# isg-pico-filter-breakout-rev1.net
KiCad netlist of a schematic drawn in EAGLE
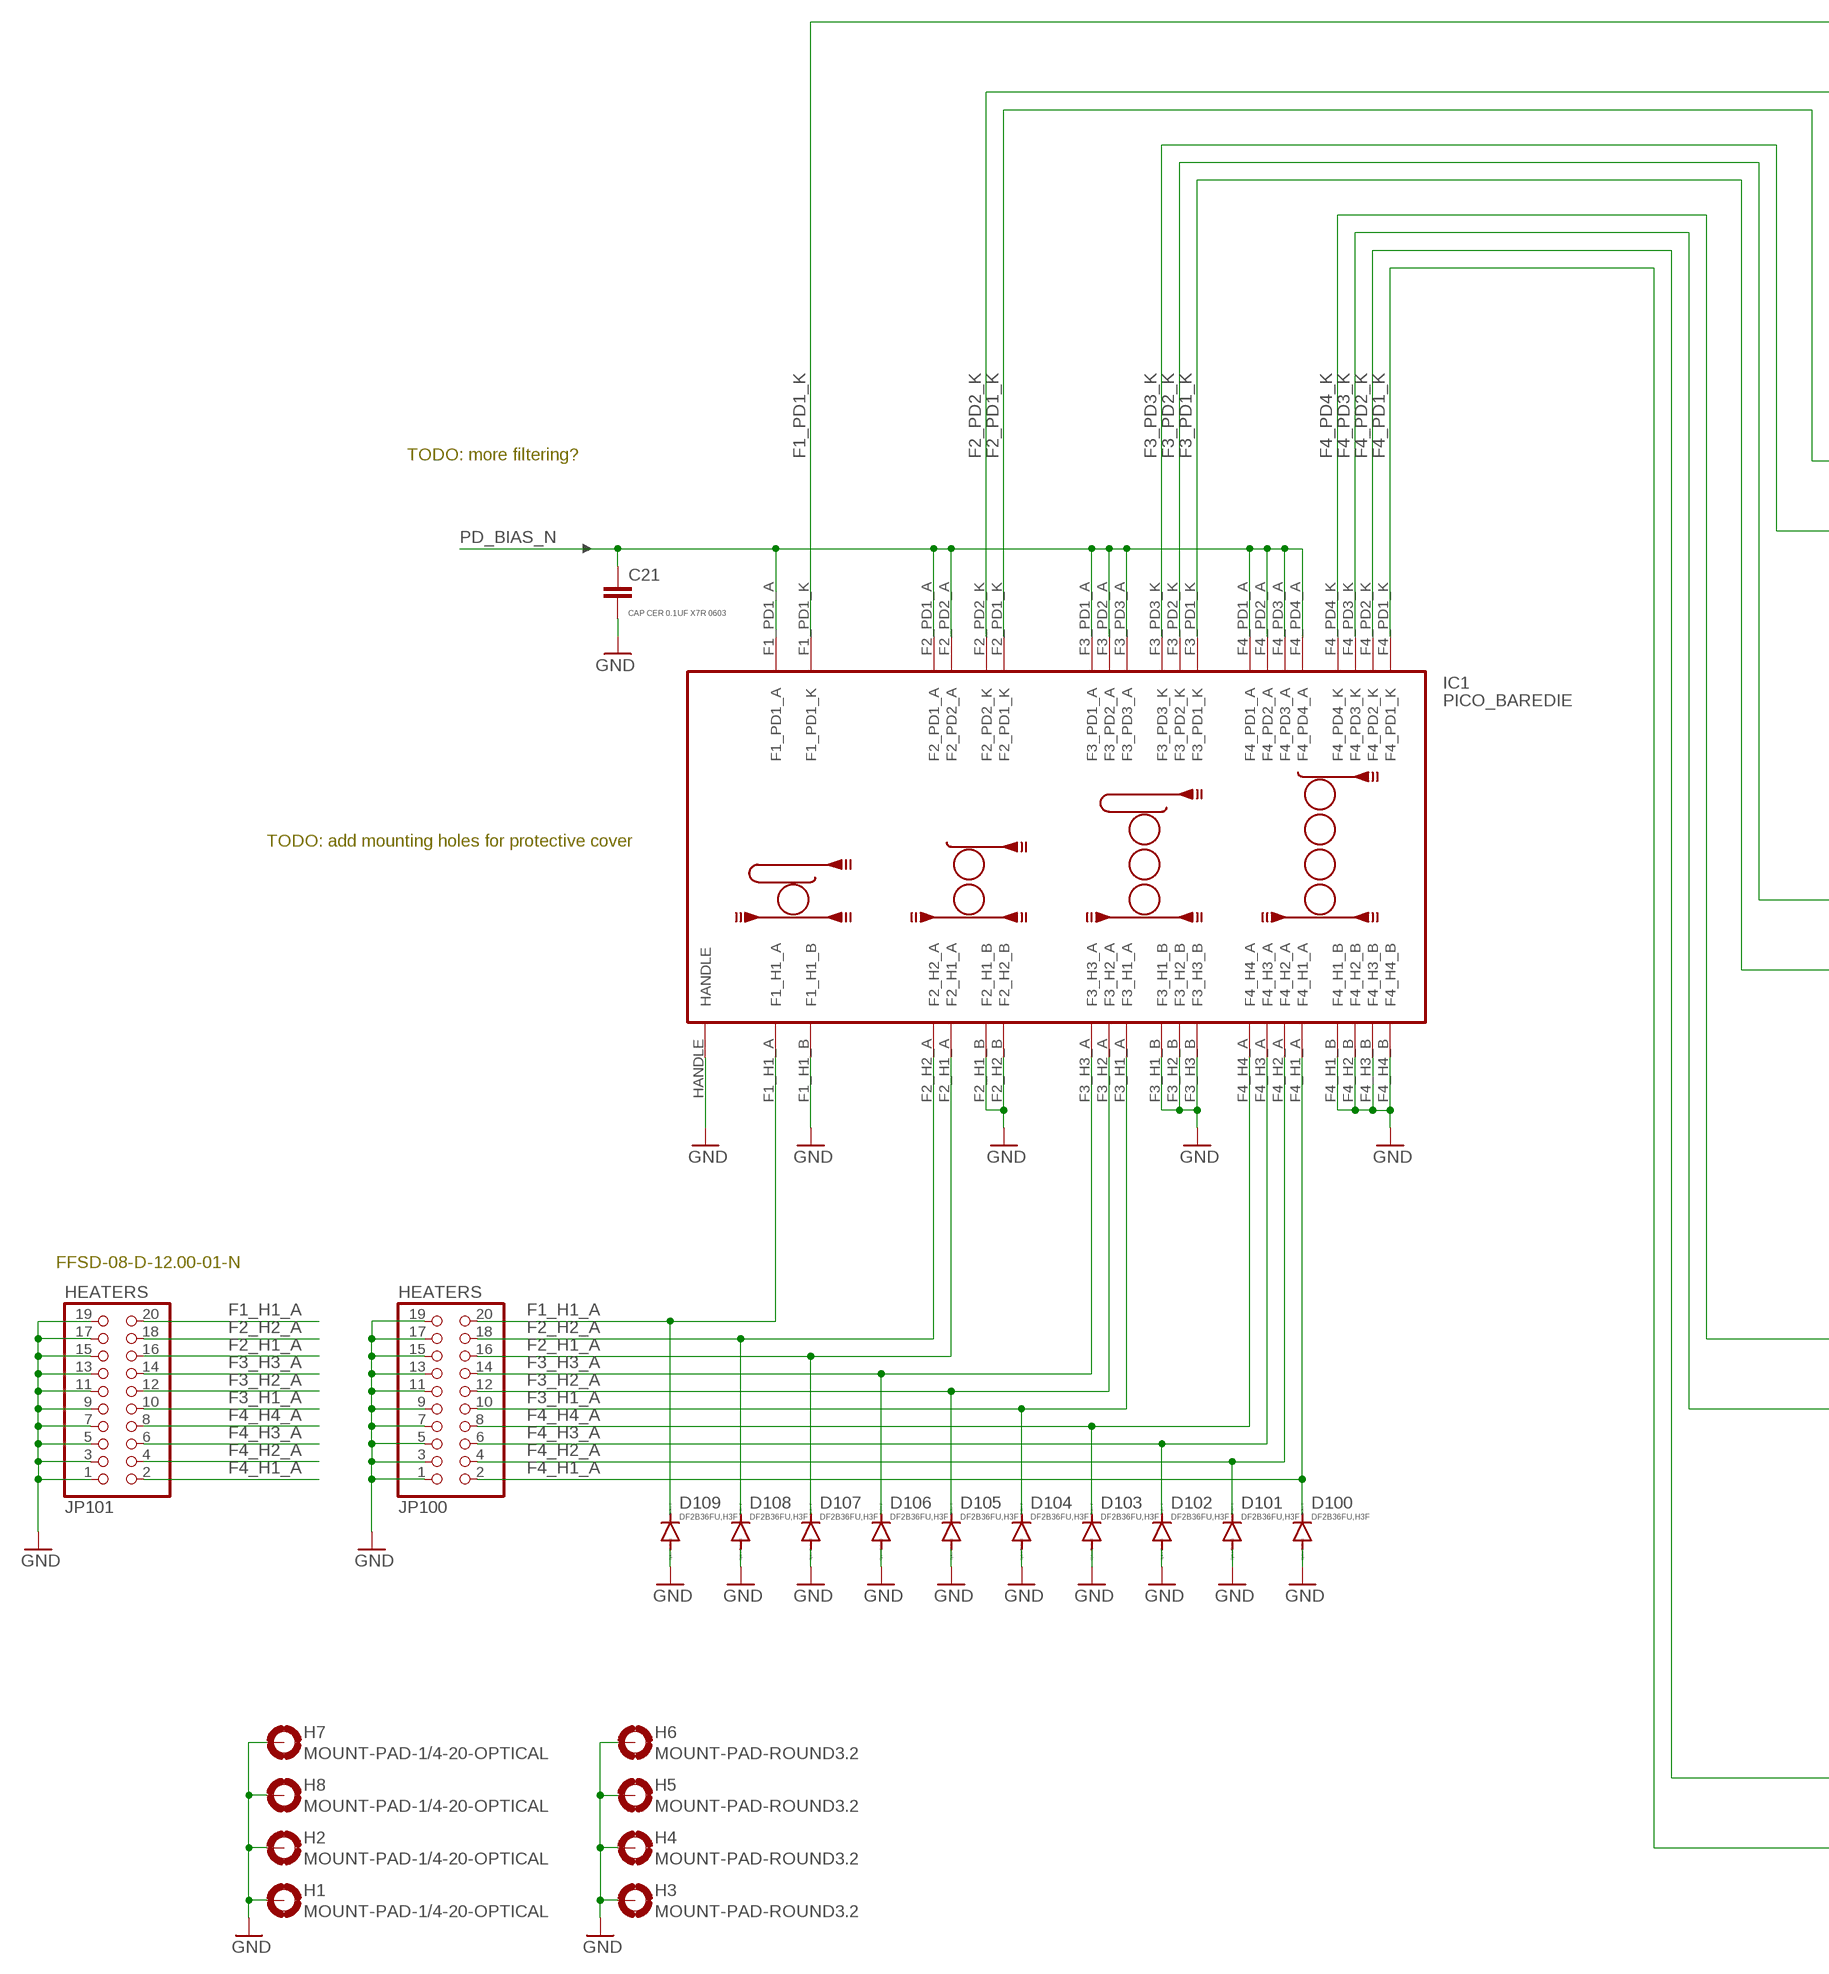
[diagram p0: schematic, sheet 1, part 1 of 2]
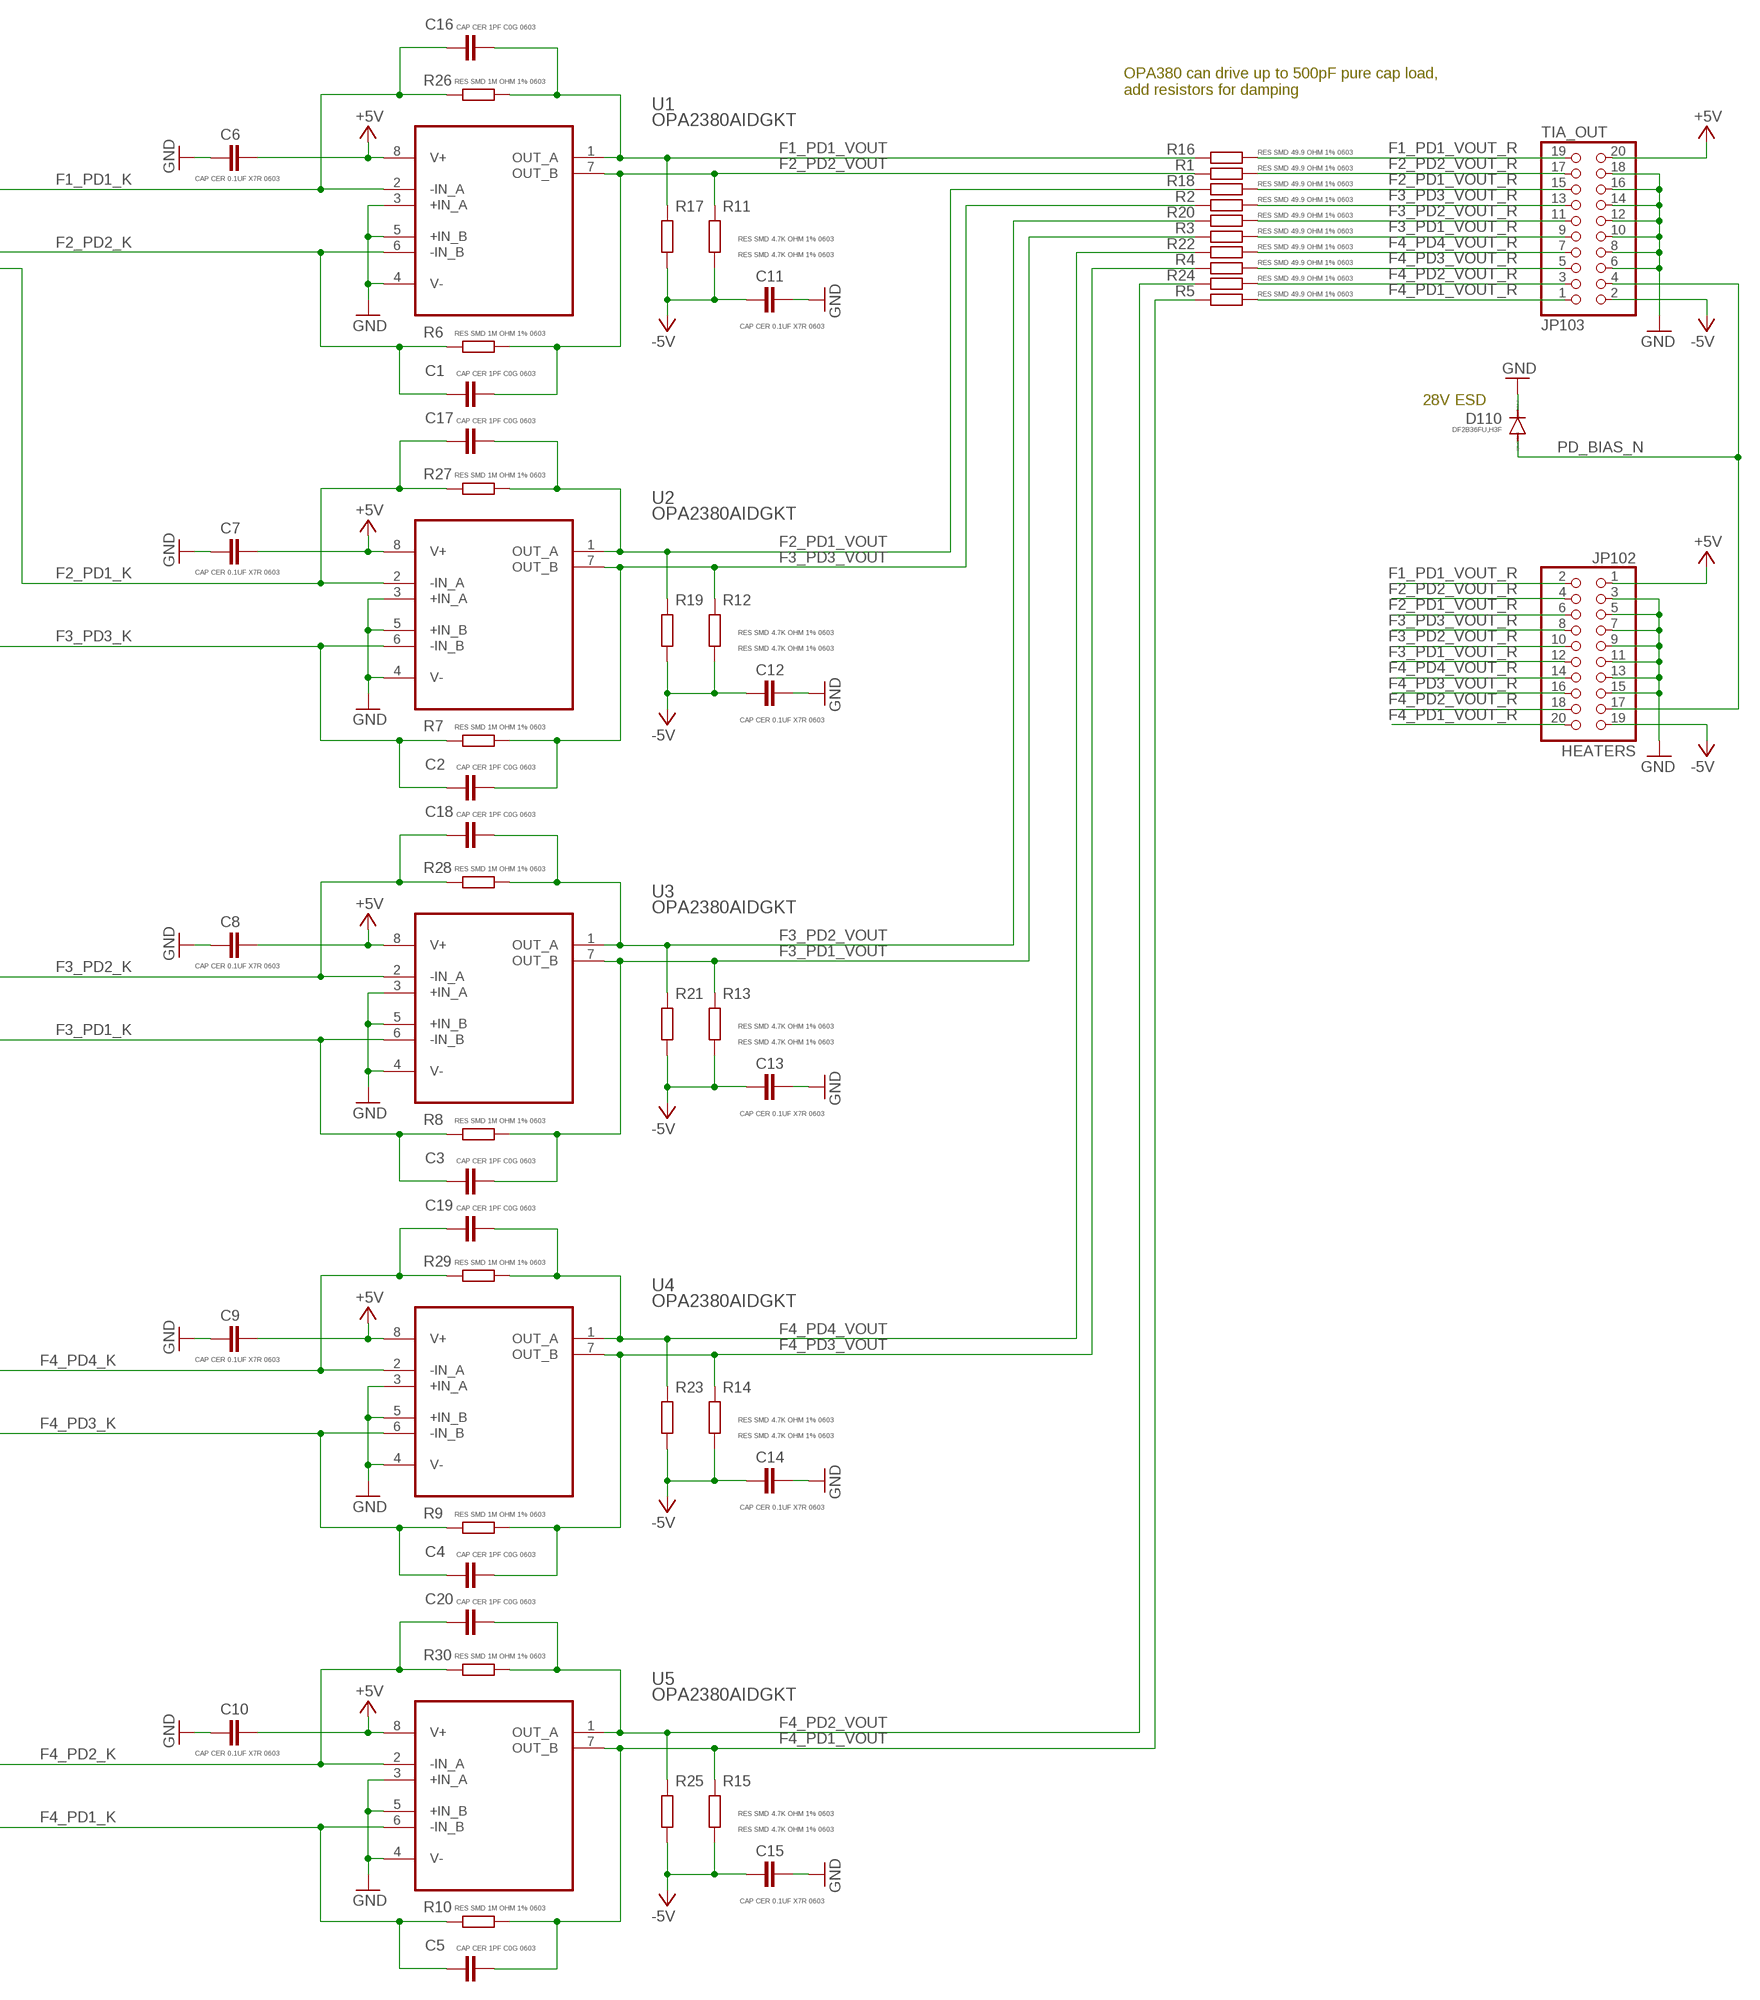
[diagram p1: schematic, sheet 1, part 2 of 2]

(export (version "E")
  (design (tool "Eeschema 10.0.6"))
  (components
    (comp (ref "C1")
      (value "CAP CER 1PF C0G 0603")
      (footprint "eagle-import:C0603")
      (libsource (lib "eagle-import") (part "C-EUC0603"))
    )
    (comp (ref "C2")
      (value "CAP CER 1PF C0G 0603")
      (footprint "eagle-import:C0603")
      (libsource (lib "eagle-import") (part "C-EUC0603"))
    )
    (comp (ref "C3")
      (value "CAP CER 1PF C0G 0603")
      (footprint "eagle-import:C0603")
      (libsource (lib "eagle-import") (part "C-EUC0603"))
    )
    (comp (ref "C4")
      (value "CAP CER 1PF C0G 0603")
      (footprint "eagle-import:C0603")
      (libsource (lib "eagle-import") (part "C-EUC0603"))
    )
    (comp (ref "C5")
      (value "CAP CER 1PF C0G 0603")
      (footprint "eagle-import:C0603")
      (libsource (lib "eagle-import") (part "C-EUC0603"))
    )
    (comp (ref "C6")
      (value "CAP CER 0.1UF X7R 0603")
      (footprint "eagle-import:C0603")
      (libsource (lib "eagle-import") (part "C-EUC0603"))
    )
    (comp (ref "C7")
      (value "CAP CER 0.1UF X7R 0603")
      (footprint "eagle-import:C0603")
      (libsource (lib "eagle-import") (part "C-EUC0603"))
    )
    (comp (ref "C8")
      (value "CAP CER 0.1UF X7R 0603")
      (footprint "eagle-import:C0603")
      (libsource (lib "eagle-import") (part "C-EUC0603"))
    )
    (comp (ref "C9")
      (value "CAP CER 0.1UF X7R 0603")
      (footprint "eagle-import:C0603")
      (libsource (lib "eagle-import") (part "C-EUC0603"))
    )
    (comp (ref "C10")
      (value "CAP CER 0.1UF X7R 0603")
      (footprint "eagle-import:C0603")
      (libsource (lib "eagle-import") (part "C-EUC0603"))
    )
    (comp (ref "C11")
      (value "CAP CER 0.1UF X7R 0603")
      (footprint "eagle-import:C0603")
      (libsource (lib "eagle-import") (part "C-EUC0603"))
    )
    (comp (ref "C12")
      (value "CAP CER 0.1UF X7R 0603")
      (footprint "eagle-import:C0603")
      (libsource (lib "eagle-import") (part "C-EUC0603"))
    )
    (comp (ref "C13")
      (value "CAP CER 0.1UF X7R 0603")
      (footprint "eagle-import:C0603")
      (libsource (lib "eagle-import") (part "C-EUC0603"))
    )
    (comp (ref "C14")
      (value "CAP CER 0.1UF X7R 0603")
      (footprint "eagle-import:C0603")
      (libsource (lib "eagle-import") (part "C-EUC0603"))
    )
    (comp (ref "C15")
      (value "CAP CER 0.1UF X7R 0603")
      (footprint "eagle-import:C0603")
      (libsource (lib "eagle-import") (part "C-EUC0603"))
    )
    (comp (ref "C16")
      (value "CAP CER 1PF C0G 0603")
      (footprint "eagle-import:C0603")
      (libsource (lib "eagle-import") (part "C-EUC0603"))
    )
    (comp (ref "C17")
      (value "CAP CER 1PF C0G 0603")
      (footprint "eagle-import:C0603")
      (libsource (lib "eagle-import") (part "C-EUC0603"))
    )
    (comp (ref "C18")
      (value "CAP CER 1PF C0G 0603")
      (footprint "eagle-import:C0603")
      (libsource (lib "eagle-import") (part "C-EUC0603"))
    )
    (comp (ref "C19")
      (value "CAP CER 1PF C0G 0603")
      (footprint "eagle-import:C0603")
      (libsource (lib "eagle-import") (part "C-EUC0603"))
    )
    (comp (ref "C20")
      (value "CAP CER 1PF C0G 0603")
      (footprint "eagle-import:C0603")
      (libsource (lib "eagle-import") (part "C-EUC0603"))
    )
    (comp (ref "C21")
      (value "CAP CER 0.1UF X7R 0603")
      (footprint "eagle-import:C0603")
      (libsource (lib "eagle-import") (part "C-EUC0603"))
    )
    (comp (ref "D100")
      (value "DF2B36FU,H3F")
      (footprint "eagle-import:SOD323-W")
      (libsource (lib "eagle-import") (part "DIODE-SOD323-W"))
    )
    (comp (ref "D101")
      (value "DF2B36FU,H3F")
      (footprint "eagle-import:SOD323-W")
      (libsource (lib "eagle-import") (part "DIODE-SOD323-W"))
    )
    (comp (ref "D102")
      (value "DF2B36FU,H3F")
      (footprint "eagle-import:SOD323-W")
      (libsource (lib "eagle-import") (part "DIODE-SOD323-W"))
    )
    (comp (ref "D103")
      (value "DF2B36FU,H3F")
      (footprint "eagle-import:SOD323-W")
      (libsource (lib "eagle-import") (part "DIODE-SOD323-W"))
    )
    (comp (ref "D104")
      (value "DF2B36FU,H3F")
      (footprint "eagle-import:SOD323-W")
      (libsource (lib "eagle-import") (part "DIODE-SOD323-W"))
    )
    (comp (ref "D105")
      (value "DF2B36FU,H3F")
      (footprint "eagle-import:SOD323-W")
      (libsource (lib "eagle-import") (part "DIODE-SOD323-W"))
    )
    (comp (ref "D106")
      (value "DF2B36FU,H3F")
      (footprint "eagle-import:SOD323-W")
      (libsource (lib "eagle-import") (part "DIODE-SOD323-W"))
    )
    (comp (ref "D107")
      (value "DF2B36FU,H3F")
      (footprint "eagle-import:SOD323-W")
      (libsource (lib "eagle-import") (part "DIODE-SOD323-W"))
    )
    (comp (ref "D108")
      (value "DF2B36FU,H3F")
      (footprint "eagle-import:SOD323-W")
      (libsource (lib "eagle-import") (part "DIODE-SOD323-W"))
    )
    (comp (ref "D109")
      (value "DF2B36FU,H3F")
      (footprint "eagle-import:SOD323-W")
      (libsource (lib "eagle-import") (part "DIODE-SOD323-W"))
    )
    (comp (ref "D110")
      (value "DF2B36FU,H3F")
      (footprint "eagle-import:SOD323-W")
      (libsource (lib "eagle-import") (part "DIODE-SOD323-W"))
    )
    (comp (ref "H1")
      (value "MOUNT-PAD-1/4-20-OPTICAL")
      (footprint "eagle-import:MOUNT-PAD-1_4-20")
      (libsource (lib "eagle-import") (part "MOUNT-PAD-1/4-20-OPTICAL"))
    )
    (comp (ref "H2")
      (value "MOUNT-PAD-1/4-20-OPTICAL")
      (footprint "eagle-import:MOUNT-PAD-1_4-20")
      (libsource (lib "eagle-import") (part "MOUNT-PAD-1/4-20-OPTICAL"))
    )
    (comp (ref "H3")
      (value "MOUNT-PAD-ROUND3.2")
      (footprint "eagle-import:3,2-PAD")
      (libsource (lib "eagle-import") (part "MOUNT-PAD-ROUND3.2"))
    )
    (comp (ref "H4")
      (value "MOUNT-PAD-ROUND3.2")
      (footprint "eagle-import:3,2-PAD")
      (libsource (lib "eagle-import") (part "MOUNT-PAD-ROUND3.2"))
    )
    (comp (ref "H5")
      (value "MOUNT-PAD-ROUND3.2")
      (footprint "eagle-import:3,2-PAD")
      (libsource (lib "eagle-import") (part "MOUNT-PAD-ROUND3.2"))
    )
    (comp (ref "H6")
      (value "MOUNT-PAD-ROUND3.2")
      (footprint "eagle-import:3,2-PAD")
      (libsource (lib "eagle-import") (part "MOUNT-PAD-ROUND3.2"))
    )
    (comp (ref "H7")
      (value "MOUNT-PAD-1/4-20-OPTICAL")
      (footprint "eagle-import:MOUNT-PAD-1_4-20")
      (libsource (lib "eagle-import") (part "MOUNT-PAD-1/4-20-OPTICAL"))
    )
    (comp (ref "H8")
      (value "MOUNT-PAD-1/4-20-OPTICAL")
      (footprint "eagle-import:MOUNT-PAD-1_4-20")
      (libsource (lib "eagle-import") (part "MOUNT-PAD-1/4-20-OPTICAL"))
    )
    (comp (ref "IC1")
      (value "PICO_BAREDIE")
      (footprint "eagle-import:DIE-PICO-MULTI-RING-FILTERS")
      (libsource (lib "eagle-import") (part "DIE-PICO-MULTI-RING-FILTERS"))
    )
    (comp (ref "JP100")
      (value "HEATERS")
      (footprint "eagle-import:2X10")
      (libsource (lib "eagle-import") (part "PINHD-2X10"))
    )
    (comp (ref "JP101")
      (value "HEATERS")
      (footprint "eagle-import:FTSH-110-01-L-DV-K-TR")
      (libsource (lib "eagle-import") (part "FFSD-08-D-12.00-01-N"))
    )
    (comp (ref "JP102")
      (value "HEATERS")
      (footprint "eagle-import:FTSH-110-01-L-DV-K-TR")
      (libsource (lib "eagle-import") (part "FFSD-08-D-12.00-01-N"))
    )
    (comp (ref "JP103")
      (value "TIA_OUT")
      (footprint "eagle-import:2X10")
      (libsource (lib "eagle-import") (part "PINHD-2X10"))
    )
    (comp (ref "R1")
      (value "RES SMD 49.9 OHM 1% 0603")
      (footprint "eagle-import:R0603")
      (libsource (lib "eagle-import") (part "R-EU_R0603"))
    )
    (comp (ref "R2")
      (value "RES SMD 49.9 OHM 1% 0603")
      (footprint "eagle-import:R0603")
      (libsource (lib "eagle-import") (part "R-EU_R0603"))
    )
    (comp (ref "R3")
      (value "RES SMD 49.9 OHM 1% 0603")
      (footprint "eagle-import:R0603")
      (libsource (lib "eagle-import") (part "R-EU_R0603"))
    )
    (comp (ref "R4")
      (value "RES SMD 49.9 OHM 1% 0603")
      (footprint "eagle-import:R0603")
      (libsource (lib "eagle-import") (part "R-EU_R0603"))
    )
    (comp (ref "R5")
      (value "RES SMD 49.9 OHM 1% 0603")
      (footprint "eagle-import:R0603")
      (libsource (lib "eagle-import") (part "R-EU_R0603"))
    )
    (comp (ref "R6")
      (value "RES SMD 1M OHM 1% 0603")
      (footprint "eagle-import:R0603")
      (libsource (lib "eagle-import") (part "R-EU_R0603"))
    )
    (comp (ref "R7")
      (value "RES SMD 1M OHM 1% 0603")
      (footprint "eagle-import:R0603")
      (libsource (lib "eagle-import") (part "R-EU_R0603"))
    )
    (comp (ref "R8")
      (value "RES SMD 1M OHM 1% 0603")
      (footprint "eagle-import:R0603")
      (libsource (lib "eagle-import") (part "R-EU_R0603"))
    )
    (comp (ref "R9")
      (value "RES SMD 1M OHM 1% 0603")
      (footprint "eagle-import:R0603")
      (libsource (lib "eagle-import") (part "R-EU_R0603"))
    )
    (comp (ref "R10")
      (value "RES SMD 1M OHM 1% 0603")
      (footprint "eagle-import:R0603")
      (libsource (lib "eagle-import") (part "R-EU_R0603"))
    )
    (comp (ref "R11")
      (value "RES SMD 4.7K OHM 1% 0603")
      (footprint "eagle-import:R0603")
      (libsource (lib "eagle-import") (part "R-EU_R0603"))
    )
    (comp (ref "R12")
      (value "RES SMD 4.7K OHM 1% 0603")
      (footprint "eagle-import:R0603")
      (libsource (lib "eagle-import") (part "R-EU_R0603"))
    )
    (comp (ref "R13")
      (value "RES SMD 4.7K OHM 1% 0603")
      (footprint "eagle-import:R0603")
      (libsource (lib "eagle-import") (part "R-EU_R0603"))
    )
    (comp (ref "R14")
      (value "RES SMD 4.7K OHM 1% 0603")
      (footprint "eagle-import:R0603")
      (libsource (lib "eagle-import") (part "R-EU_R0603"))
    )
    (comp (ref "R15")
      (value "RES SMD 4.7K OHM 1% 0603")
      (footprint "eagle-import:R0603")
      (libsource (lib "eagle-import") (part "R-EU_R0603"))
    )
    (comp (ref "R16")
      (value "RES SMD 49.9 OHM 1% 0603")
      (footprint "eagle-import:R0603")
      (libsource (lib "eagle-import") (part "R-EU_R0603"))
    )
    (comp (ref "R17")
      (value "RES SMD 4.7K OHM 1% 0603")
      (footprint "eagle-import:R0603")
      (libsource (lib "eagle-import") (part "R-EU_R0603"))
    )
    (comp (ref "R18")
      (value "RES SMD 49.9 OHM 1% 0603")
      (footprint "eagle-import:R0603")
      (libsource (lib "eagle-import") (part "R-EU_R0603"))
    )
    (comp (ref "R19")
      (value "RES SMD 4.7K OHM 1% 0603")
      (footprint "eagle-import:R0603")
      (libsource (lib "eagle-import") (part "R-EU_R0603"))
    )
    (comp (ref "R20")
      (value "RES SMD 49.9 OHM 1% 0603")
      (footprint "eagle-import:R0603")
      (libsource (lib "eagle-import") (part "R-EU_R0603"))
    )
    (comp (ref "R21")
      (value "RES SMD 4.7K OHM 1% 0603")
      (footprint "eagle-import:R0603")
      (libsource (lib "eagle-import") (part "R-EU_R0603"))
    )
    (comp (ref "R22")
      (value "RES SMD 49.9 OHM 1% 0603")
      (footprint "eagle-import:R0603")
      (libsource (lib "eagle-import") (part "R-EU_R0603"))
    )
    (comp (ref "R23")
      (value "RES SMD 4.7K OHM 1% 0603")
      (footprint "eagle-import:R0603")
      (libsource (lib "eagle-import") (part "R-EU_R0603"))
    )
    (comp (ref "R24")
      (value "RES SMD 49.9 OHM 1% 0603")
      (footprint "eagle-import:R0603")
      (libsource (lib "eagle-import") (part "R-EU_R0603"))
    )
    (comp (ref "R25")
      (value "RES SMD 4.7K OHM 1% 0603")
      (footprint "eagle-import:R0603")
      (libsource (lib "eagle-import") (part "R-EU_R0603"))
    )
    (comp (ref "R26")
      (value "RES SMD 1M OHM 1% 0603")
      (footprint "eagle-import:R0603")
      (libsource (lib "eagle-import") (part "R-EU_R0603"))
    )
    (comp (ref "R27")
      (value "RES SMD 1M OHM 1% 0603")
      (footprint "eagle-import:R0603")
      (libsource (lib "eagle-import") (part "R-EU_R0603"))
    )
    (comp (ref "R28")
      (value "RES SMD 1M OHM 1% 0603")
      (footprint "eagle-import:R0603")
      (libsource (lib "eagle-import") (part "R-EU_R0603"))
    )
    (comp (ref "R29")
      (value "RES SMD 1M OHM 1% 0603")
      (footprint "eagle-import:R0603")
      (libsource (lib "eagle-import") (part "R-EU_R0603"))
    )
    (comp (ref "R30")
      (value "RES SMD 1M OHM 1% 0603")
      (footprint "eagle-import:R0603")
      (libsource (lib "eagle-import") (part "R-EU_R0603"))
    )
    (comp (ref "U1")
      (value "OPA2380AIDGKT")
      (footprint "eagle-import:SOP65P490X110-8N")
      (libsource (lib "eagle-import") (part "OPA2380AIDGKT"))
    )
    (comp (ref "U2")
      (value "OPA2380AIDGKT")
      (footprint "eagle-import:SOP65P490X110-8N")
      (libsource (lib "eagle-import") (part "OPA2380AIDGKT"))
    )
    (comp (ref "U3")
      (value "OPA2380AIDGKT")
      (footprint "eagle-import:SOP65P490X110-8N")
      (libsource (lib "eagle-import") (part "OPA2380AIDGKT"))
    )
    (comp (ref "U4")
      (value "OPA2380AIDGKT")
      (footprint "eagle-import:SOP65P490X110-8N")
      (libsource (lib "eagle-import") (part "OPA2380AIDGKT"))
    )
    (comp (ref "U5")
      (value "OPA2380AIDGKT")
      (footprint "eagle-import:SOP65P490X110-8N")
      (libsource (lib "eagle-import") (part "OPA2380AIDGKT"))
    )
  )
  (nets
    (net (code "1") (name "+5V") (class "Default")
      (node (ref "C10") (pin "1") (pinfunction "1_1") (pintype "passive"))
      (node (ref "C6") (pin "1") (pinfunction "1_1") (pintype "passive"))
      (node (ref "C7") (pin "1") (pinfunction "1_1") (pintype "passive"))
      (node (ref "C8") (pin "1") (pinfunction "1_1") (pintype "passive"))
      (node (ref "C9") (pin "1") (pinfunction "1_1") (pintype "passive"))
      (node (ref "JP102") (pin "1") (pinfunction "1_1") (pintype "passive"))
      (node (ref "JP103") (pin "20") (pinfunction "20_20") (pintype "passive"))
      (node (ref "U1") (pin "8") (pinfunction "V+_8") (pintype "power_in"))
      (node (ref "U2") (pin "8") (pinfunction "V+_8") (pintype "power_in"))
      (node (ref "U3") (pin "8") (pinfunction "V+_8") (pintype "power_in"))
      (node (ref "U4") (pin "8") (pinfunction "V+_8") (pintype "power_in"))
      (node (ref "U5") (pin "8") (pinfunction "V+_8") (pintype "power_in"))
    )
    (net (code "2") (name "-5V") (class "Default")
      (node (ref "C11") (pin "2") (pinfunction "2_2") (pintype "passive"))
      (node (ref "C12") (pin "2") (pinfunction "2_2") (pintype "passive"))
      (node (ref "C13") (pin "2") (pinfunction "2_2") (pintype "passive"))
      (node (ref "C14") (pin "2") (pinfunction "2_2") (pintype "passive"))
      (node (ref "C15") (pin "2") (pinfunction "2_2") (pintype "passive"))
      (node (ref "JP102") (pin "19") (pinfunction "19_19") (pintype "passive"))
      (node (ref "JP103") (pin "2") (pinfunction "2_2") (pintype "passive"))
      (node (ref "R11") (pin "2") (pinfunction "2_2") (pintype "passive"))
      (node (ref "R12") (pin "2") (pinfunction "2_2") (pintype "passive"))
      (node (ref "R13") (pin "2") (pinfunction "2_2") (pintype "passive"))
      (node (ref "R14") (pin "2") (pinfunction "2_2") (pintype "passive"))
      (node (ref "R15") (pin "2") (pinfunction "2_2") (pintype "passive"))
      (node (ref "R17") (pin "2") (pinfunction "2_2") (pintype "passive"))
      (node (ref "R19") (pin "2") (pinfunction "2_2") (pintype "passive"))
      (node (ref "R21") (pin "2") (pinfunction "2_2") (pintype "passive"))
      (node (ref "R23") (pin "2") (pinfunction "2_2") (pintype "passive"))
      (node (ref "R25") (pin "2") (pinfunction "2_2") (pintype "passive"))
    )
    (net (code "3") (name "/F1_H1_A") (class "Default")
      (node (ref "D109") (pin "C") (pinfunction "C_C") (pintype "passive"))
      (node (ref "IC1") (pin "F1_H1_A") (pinfunction "F1_H1_A_F1_H1_A") (pintype "bidirectional"))
      (node (ref "JP100") (pin "20") (pinfunction "20_20") (pintype "passive"))
      (node (ref "JP101") (pin "20") (pinfunction "20_20") (pintype "passive"))
    )
    (net (code "4") (name "/F1_PD1_K") (class "Default")
      (node (ref "C16") (pin "1") (pinfunction "1_1") (pintype "passive"))
      (node (ref "IC1") (pin "F1_PD1_K") (pinfunction "F1_PD1_K_F1_PD1_K") (pintype "bidirectional"))
      (node (ref "R26") (pin "1") (pinfunction "1_1") (pintype "passive"))
      (node (ref "U1") (pin "2") (pinfunction "-IN_A_2") (pintype "input"))
    )
    (net (code "5") (name "/F1_PD1_VOUT") (class "Default")
      (node (ref "C16") (pin "2") (pinfunction "2_2") (pintype "passive"))
      (node (ref "R16") (pin "1") (pinfunction "1_1") (pintype "passive"))
      (node (ref "R17") (pin "1") (pinfunction "1_1") (pintype "passive"))
      (node (ref "R26") (pin "2") (pinfunction "2_2") (pintype "passive"))
      (node (ref "U1") (pin "1") (pinfunction "OUT_A_1") (pintype "output"))
    )
    (net (code "6") (name "/F1_PD1_VOUT_R") (class "Default")
      (node (ref "JP102") (pin "2") (pinfunction "2_2") (pintype "passive"))
      (node (ref "JP103") (pin "19") (pinfunction "19_19") (pintype "passive"))
      (node (ref "R16") (pin "2") (pinfunction "2_2") (pintype "passive"))
    )
    (net (code "7") (name "/F2_H1_A") (class "Default")
      (node (ref "D107") (pin "C") (pinfunction "C_C") (pintype "passive"))
      (node (ref "IC1") (pin "F2_H1_A") (pinfunction "F2_H1_A_F2_H1_A") (pintype "bidirectional"))
      (node (ref "JP100") (pin "16") (pinfunction "16_16") (pintype "passive"))
      (node (ref "JP101") (pin "16") (pinfunction "16_16") (pintype "passive"))
    )
    (net (code "8") (name "/F2_H2_A") (class "Default")
      (node (ref "D108") (pin "C") (pinfunction "C_C") (pintype "passive"))
      (node (ref "IC1") (pin "F2_H2_A") (pinfunction "F2_H2_A_F2_H2_A") (pintype "bidirectional"))
      (node (ref "JP100") (pin "18") (pinfunction "18_18") (pintype "passive"))
      (node (ref "JP101") (pin "18") (pinfunction "18_18") (pintype "passive"))
    )
    (net (code "9") (name "/F2_PD1_K") (class "Default")
      (node (ref "C17") (pin "1") (pinfunction "1_1") (pintype "passive"))
      (node (ref "IC1") (pin "F2_PD1_K") (pinfunction "F2_PD1_K_F2_PD1_K") (pintype "bidirectional"))
      (node (ref "R27") (pin "1") (pinfunction "1_1") (pintype "passive"))
      (node (ref "U2") (pin "2") (pinfunction "-IN_A_2") (pintype "input"))
    )
    (net (code "10") (name "/F2_PD1_VOUT") (class "Default")
      (node (ref "C17") (pin "2") (pinfunction "2_2") (pintype "passive"))
      (node (ref "R18") (pin "1") (pinfunction "1_1") (pintype "passive"))
      (node (ref "R19") (pin "1") (pinfunction "1_1") (pintype "passive"))
      (node (ref "R27") (pin "2") (pinfunction "2_2") (pintype "passive"))
      (node (ref "U2") (pin "1") (pinfunction "OUT_A_1") (pintype "output"))
    )
    (net (code "11") (name "/F2_PD1_VOUT_R") (class "Default")
      (node (ref "JP102") (pin "6") (pinfunction "6_6") (pintype "passive"))
      (node (ref "JP103") (pin "15") (pinfunction "15_15") (pintype "passive"))
      (node (ref "R18") (pin "2") (pinfunction "2_2") (pintype "passive"))
    )
    (net (code "12") (name "/F2_PD2_K") (class "Default")
      (node (ref "C1") (pin "1") (pinfunction "1_1") (pintype "passive"))
      (node (ref "IC1") (pin "F2_PD2_K") (pinfunction "F2_PD2_K_F2_PD2_K") (pintype "bidirectional"))
      (node (ref "R6") (pin "1") (pinfunction "1_1") (pintype "passive"))
      (node (ref "U1") (pin "6") (pinfunction "-IN_B_6") (pintype "input"))
    )
    (net (code "13") (name "/F2_PD2_VOUT") (class "Default")
      (node (ref "C1") (pin "2") (pinfunction "2_2") (pintype "passive"))
      (node (ref "R1") (pin "1") (pinfunction "1_1") (pintype "passive"))
      (node (ref "R11") (pin "1") (pinfunction "1_1") (pintype "passive"))
      (node (ref "R6") (pin "2") (pinfunction "2_2") (pintype "passive"))
      (node (ref "U1") (pin "7") (pinfunction "OUT_B_7") (pintype "output"))
    )
    (net (code "14") (name "/F2_PD2_VOUT_R") (class "Default")
      (node (ref "JP102") (pin "4") (pinfunction "4_4") (pintype "passive"))
      (node (ref "JP103") (pin "17") (pinfunction "17_17") (pintype "passive"))
      (node (ref "R1") (pin "2") (pinfunction "2_2") (pintype "passive"))
    )
    (net (code "15") (name "/F3_H1_A") (class "Default")
      (node (ref "D104") (pin "C") (pinfunction "C_C") (pintype "passive"))
      (node (ref "IC1") (pin "F3_H1_A") (pinfunction "F3_H1_A_F3_H1_A") (pintype "bidirectional"))
      (node (ref "JP100") (pin "10") (pinfunction "10_10") (pintype "passive"))
      (node (ref "JP101") (pin "10") (pinfunction "10_10") (pintype "passive"))
    )
    (net (code "16") (name "/F3_H2_A") (class "Default")
      (node (ref "D105") (pin "C") (pinfunction "C_C") (pintype "passive"))
      (node (ref "IC1") (pin "F3_H2_A") (pinfunction "F3_H2_A_F3_H2_A") (pintype "bidirectional"))
      (node (ref "JP100") (pin "12") (pinfunction "12_12") (pintype "passive"))
      (node (ref "JP101") (pin "12") (pinfunction "12_12") (pintype "passive"))
    )
    (net (code "17") (name "/F3_H3_A") (class "Default")
      (node (ref "D106") (pin "C") (pinfunction "C_C") (pintype "passive"))
      (node (ref "IC1") (pin "F3_H3_A") (pinfunction "F3_H3_A_F3_H3_A") (pintype "bidirectional"))
      (node (ref "JP100") (pin "14") (pinfunction "14_14") (pintype "passive"))
      (node (ref "JP101") (pin "14") (pinfunction "14_14") (pintype "passive"))
    )
    (net (code "18") (name "/F3_PD1_K") (class "Default")
      (node (ref "C3") (pin "1") (pinfunction "1_1") (pintype "passive"))
      (node (ref "IC1") (pin "F3_PD1_K") (pinfunction "F3_PD1_K_F3_PD1_K") (pintype "bidirectional"))
      (node (ref "R8") (pin "1") (pinfunction "1_1") (pintype "passive"))
      (node (ref "U3") (pin "6") (pinfunction "-IN_B_6") (pintype "input"))
    )
    (net (code "19") (name "/F3_PD1_VOUT") (class "Default")
      (node (ref "C3") (pin "2") (pinfunction "2_2") (pintype "passive"))
      (node (ref "R13") (pin "1") (pinfunction "1_1") (pintype "passive"))
      (node (ref "R3") (pin "1") (pinfunction "1_1") (pintype "passive"))
      (node (ref "R8") (pin "2") (pinfunction "2_2") (pintype "passive"))
      (node (ref "U3") (pin "7") (pinfunction "OUT_B_7") (pintype "output"))
    )
    (net (code "20") (name "/F3_PD1_VOUT_R") (class "Default")
      (node (ref "JP102") (pin "12") (pinfunction "12_12") (pintype "passive"))
      (node (ref "JP103") (pin "9") (pinfunction "9_9") (pintype "passive"))
      (node (ref "R3") (pin "2") (pinfunction "2_2") (pintype "passive"))
    )
    (net (code "21") (name "/F3_PD2_K") (class "Default")
      (node (ref "C18") (pin "1") (pinfunction "1_1") (pintype "passive"))
      (node (ref "IC1") (pin "F3_PD2_K") (pinfunction "F3_PD2_K_F3_PD2_K") (pintype "bidirectional"))
      (node (ref "R28") (pin "1") (pinfunction "1_1") (pintype "passive"))
      (node (ref "U3") (pin "2") (pinfunction "-IN_A_2") (pintype "input"))
    )
    (net (code "22") (name "/F3_PD2_VOUT") (class "Default")
      (node (ref "C18") (pin "2") (pinfunction "2_2") (pintype "passive"))
      (node (ref "R20") (pin "1") (pinfunction "1_1") (pintype "passive"))
      (node (ref "R21") (pin "1") (pinfunction "1_1") (pintype "passive"))
      (node (ref "R28") (pin "2") (pinfunction "2_2") (pintype "passive"))
      (node (ref "U3") (pin "1") (pinfunction "OUT_A_1") (pintype "output"))
    )
    (net (code "23") (name "/F3_PD2_VOUT_R") (class "Default")
      (node (ref "JP102") (pin "10") (pinfunction "10_10") (pintype "passive"))
      (node (ref "JP103") (pin "11") (pinfunction "11_11") (pintype "passive"))
      (node (ref "R20") (pin "2") (pinfunction "2_2") (pintype "passive"))
    )
    (net (code "24") (name "/F3_PD3_K") (class "Default")
      (node (ref "C2") (pin "1") (pinfunction "1_1") (pintype "passive"))
      (node (ref "IC1") (pin "F3_PD3_K") (pinfunction "F3_PD3_K_F3_PD3_K") (pintype "bidirectional"))
      (node (ref "R7") (pin "1") (pinfunction "1_1") (pintype "passive"))
      (node (ref "U2") (pin "6") (pinfunction "-IN_B_6") (pintype "input"))
    )
    (net (code "25") (name "/F3_PD3_VOUT") (class "Default")
      (node (ref "C2") (pin "2") (pinfunction "2_2") (pintype "passive"))
      (node (ref "R12") (pin "1") (pinfunction "1_1") (pintype "passive"))
      (node (ref "R2") (pin "1") (pinfunction "1_1") (pintype "passive"))
      (node (ref "R7") (pin "2") (pinfunction "2_2") (pintype "passive"))
      (node (ref "U2") (pin "7") (pinfunction "OUT_B_7") (pintype "output"))
    )
    (net (code "26") (name "/F3_PD3_VOUT_R") (class "Default")
      (node (ref "JP102") (pin "8") (pinfunction "8_8") (pintype "passive"))
      (node (ref "JP103") (pin "13") (pinfunction "13_13") (pintype "passive"))
      (node (ref "R2") (pin "2") (pinfunction "2_2") (pintype "passive"))
    )
    (net (code "27") (name "/F4_H1_A") (class "Default")
      (node (ref "D100") (pin "C") (pinfunction "C_C") (pintype "passive"))
      (node (ref "IC1") (pin "F4_H1_A") (pinfunction "F4_H1_A_F4_H1_A") (pintype "bidirectional"))
      (node (ref "JP100") (pin "2") (pinfunction "2_2") (pintype "passive"))
      (node (ref "JP101") (pin "2") (pinfunction "2_2") (pintype "passive"))
    )
    (net (code "28") (name "/F4_H2_A") (class "Default")
      (node (ref "D101") (pin "C") (pinfunction "C_C") (pintype "passive"))
      (node (ref "IC1") (pin "F4_H2_A") (pinfunction "F4_H2_A_F4_H2_A") (pintype "bidirectional"))
      (node (ref "JP100") (pin "4") (pinfunction "4_4") (pintype "passive"))
      (node (ref "JP101") (pin "4") (pinfunction "4_4") (pintype "passive"))
    )
    (net (code "29") (name "/F4_H3_A") (class "Default")
      (node (ref "D102") (pin "C") (pinfunction "C_C") (pintype "passive"))
      (node (ref "IC1") (pin "F4_H3_A") (pinfunction "F4_H3_A_F4_H3_A") (pintype "bidirectional"))
      (node (ref "JP100") (pin "6") (pinfunction "6_6") (pintype "passive"))
      (node (ref "JP101") (pin "6") (pinfunction "6_6") (pintype "passive"))
    )
    (net (code "30") (name "/F4_H4_A") (class "Default")
      (node (ref "D103") (pin "C") (pinfunction "C_C") (pintype "passive"))
      (node (ref "IC1") (pin "F4_H4_A") (pinfunction "F4_H4_A_F4_H4_A") (pintype "bidirectional"))
      (node (ref "JP100") (pin "8") (pinfunction "8_8") (pintype "passive"))
      (node (ref "JP101") (pin "8") (pinfunction "8_8") (pintype "passive"))
    )
    (net (code "31") (name "/F4_PD1_K") (class "Default")
      (node (ref "C5") (pin "1") (pinfunction "1_1") (pintype "passive"))
      (node (ref "IC1") (pin "F4_PD1_K") (pinfunction "F4_PD1_K_F4_PD1_K") (pintype "bidirectional"))
      (node (ref "R10") (pin "1") (pinfunction "1_1") (pintype "passive"))
      (node (ref "U5") (pin "6") (pinfunction "-IN_B_6") (pintype "input"))
    )
    (net (code "32") (name "/F4_PD1_VOUT") (class "Default")
      (node (ref "C5") (pin "2") (pinfunction "2_2") (pintype "passive"))
      (node (ref "R10") (pin "2") (pinfunction "2_2") (pintype "passive"))
      (node (ref "R15") (pin "1") (pinfunction "1_1") (pintype "passive"))
      (node (ref "R5") (pin "1") (pinfunction "1_1") (pintype "passive"))
      (node (ref "U5") (pin "7") (pinfunction "OUT_B_7") (pintype "output"))
    )
    (net (code "33") (name "/F4_PD1_VOUT_R") (class "Default")
      (node (ref "JP102") (pin "20") (pinfunction "20_20") (pintype "passive"))
      (node (ref "JP103") (pin "1") (pinfunction "1_1") (pintype "passive"))
      (node (ref "R5") (pin "2") (pinfunction "2_2") (pintype "passive"))
    )
    (net (code "34") (name "/F4_PD2_K") (class "Default")
      (node (ref "C20") (pin "1") (pinfunction "1_1") (pintype "passive"))
      (node (ref "IC1") (pin "F4_PD2_K") (pinfunction "F4_PD2_K_F4_PD2_K") (pintype "bidirectional"))
      (node (ref "R30") (pin "1") (pinfunction "1_1") (pintype "passive"))
      (node (ref "U5") (pin "2") (pinfunction "-IN_A_2") (pintype "input"))
    )
    (net (code "35") (name "/F4_PD2_VOUT") (class "Default")
      (node (ref "C20") (pin "2") (pinfunction "2_2") (pintype "passive"))
      (node (ref "R24") (pin "1") (pinfunction "1_1") (pintype "passive"))
      (node (ref "R25") (pin "1") (pinfunction "1_1") (pintype "passive"))
      (node (ref "R30") (pin "2") (pinfunction "2_2") (pintype "passive"))
      (node (ref "U5") (pin "1") (pinfunction "OUT_A_1") (pintype "output"))
    )
    (net (code "36") (name "/F4_PD2_VOUT_R") (class "Default")
      (node (ref "JP102") (pin "18") (pinfunction "18_18") (pintype "passive"))
      (node (ref "JP103") (pin "3") (pinfunction "3_3") (pintype "passive"))
      (node (ref "R24") (pin "2") (pinfunction "2_2") (pintype "passive"))
    )
    (net (code "37") (name "/F4_PD3_K") (class "Default")
      (node (ref "C4") (pin "1") (pinfunction "1_1") (pintype "passive"))
      (node (ref "IC1") (pin "F4_PD3_K") (pinfunction "F4_PD3_K_F4_PD3_K") (pintype "bidirectional"))
      (node (ref "R9") (pin "1") (pinfunction "1_1") (pintype "passive"))
      (node (ref "U4") (pin "6") (pinfunction "-IN_B_6") (pintype "input"))
    )
    (net (code "38") (name "/F4_PD3_VOUT") (class "Default")
      (node (ref "C4") (pin "2") (pinfunction "2_2") (pintype "passive"))
      (node (ref "R14") (pin "1") (pinfunction "1_1") (pintype "passive"))
      (node (ref "R4") (pin "1") (pinfunction "1_1") (pintype "passive"))
      (node (ref "R9") (pin "2") (pinfunction "2_2") (pintype "passive"))
      (node (ref "U4") (pin "7") (pinfunction "OUT_B_7") (pintype "output"))
    )
    (net (code "39") (name "/F4_PD3_VOUT_R") (class "Default")
      (node (ref "JP102") (pin "16") (pinfunction "16_16") (pintype "passive"))
      (node (ref "JP103") (pin "5") (pinfunction "5_5") (pintype "passive"))
      (node (ref "R4") (pin "2") (pinfunction "2_2") (pintype "passive"))
    )
    (net (code "40") (name "/F4_PD4_K") (class "Default")
      (node (ref "C19") (pin "1") (pinfunction "1_1") (pintype "passive"))
      (node (ref "IC1") (pin "F4_PD4_K") (pinfunction "F4_PD4_K_F4_PD4_K") (pintype "bidirectional"))
      (node (ref "R29") (pin "1") (pinfunction "1_1") (pintype "passive"))
      (node (ref "U4") (pin "2") (pinfunction "-IN_A_2") (pintype "input"))
    )
    (net (code "41") (name "/F4_PD4_VOUT") (class "Default")
      (node (ref "C19") (pin "2") (pinfunction "2_2") (pintype "passive"))
      (node (ref "R22") (pin "1") (pinfunction "1_1") (pintype "passive"))
      (node (ref "R23") (pin "1") (pinfunction "1_1") (pintype "passive"))
      (node (ref "R29") (pin "2") (pinfunction "2_2") (pintype "passive"))
      (node (ref "U4") (pin "1") (pinfunction "OUT_A_1") (pintype "output"))
    )
    (net (code "42") (name "/F4_PD4_VOUT_R") (class "Default")
      (node (ref "JP102") (pin "14") (pinfunction "14_14") (pintype "passive"))
      (node (ref "JP103") (pin "7") (pinfunction "7_7") (pintype "passive"))
      (node (ref "R22") (pin "2") (pinfunction "2_2") (pintype "passive"))
    )
    (net (code "43") (name "/PD_BIAS_N") (class "Default")
      (node (ref "C21") (pin "1") (pinfunction "1_1") (pintype "passive"))
      (node (ref "D110") (pin "A") (pinfunction "A_A") (pintype "passive"))
      (node (ref "IC1") (pin "F1_PD1_A") (pinfunction "F1_PD1_A_F1_PD1_A") (pintype "bidirectional"))
      (node (ref "IC1") (pin "F2_PD1_A") (pinfunction "F2_PD1_A_F2_PD1_A") (pintype "bidirectional"))
      (node (ref "IC1") (pin "F2_PD2_A") (pinfunction "F2_PD2_A_F2_PD2_A") (pintype "bidirectional"))
      (node (ref "IC1") (pin "F3_PD1_A") (pinfunction "F3_PD1_A_F3_PD1_A") (pintype "bidirectional"))
      (node (ref "IC1") (pin "F3_PD2_A") (pinfunction "F3_PD2_A_F3_PD2_A") (pintype "bidirectional"))
      (node (ref "IC1") (pin "F3_PD3_A") (pinfunction "F3_PD3_A_F3_PD3_A") (pintype "bidirectional"))
      (node (ref "IC1") (pin "F4_PD1_A") (pinfunction "F4_PD1_A_F4_PD1_A") (pintype "bidirectional"))
      (node (ref "IC1") (pin "F4_PD2_A") (pinfunction "F4_PD2_A_F4_PD2_A") (pintype "bidirectional"))
      (node (ref "IC1") (pin "F4_PD3_A") (pinfunction "F4_PD3_A_F4_PD3_A") (pintype "bidirectional"))
      (node (ref "IC1") (pin "F4_PD4_A") (pinfunction "F4_PD4_A_F4_PD4_A") (pintype "bidirectional"))
      (node (ref "JP102") (pin "17") (pinfunction "17_17") (pintype "passive"))
      (node (ref "JP103") (pin "4") (pinfunction "4_4") (pintype "passive"))
    )
    (net (code "44") (name "GND") (class "Default")
      (node (ref "C10") (pin "2") (pinfunction "2_2") (pintype "passive"))
      (node (ref "C11") (pin "1") (pinfunction "1_1") (pintype "passive"))
      (node (ref "C12") (pin "1") (pinfunction "1_1") (pintype "passive"))
      (node (ref "C13") (pin "1") (pinfunction "1_1") (pintype "passive"))
      (node (ref "C14") (pin "1") (pinfunction "1_1") (pintype "passive"))
      (node (ref "C15") (pin "1") (pinfunction "1_1") (pintype "passive"))
      (node (ref "C21") (pin "2") (pinfunction "2_2") (pintype "passive"))
      (node (ref "C6") (pin "2") (pinfunction "2_2") (pintype "passive"))
      (node (ref "C7") (pin "2") (pinfunction "2_2") (pintype "passive"))
      (node (ref "C8") (pin "2") (pinfunction "2_2") (pintype "passive"))
      (node (ref "C9") (pin "2") (pinfunction "2_2") (pintype "passive"))
      (node (ref "D100") (pin "A") (pinfunction "A_A") (pintype "passive"))
      (node (ref "D101") (pin "A") (pinfunction "A_A") (pintype "passive"))
      (node (ref "D102") (pin "A") (pinfunction "A_A") (pintype "passive"))
      (node (ref "D103") (pin "A") (pinfunction "A_A") (pintype "passive"))
      (node (ref "D104") (pin "A") (pinfunction "A_A") (pintype "passive"))
      (node (ref "D105") (pin "A") (pinfunction "A_A") (pintype "passive"))
      (node (ref "D106") (pin "A") (pinfunction "A_A") (pintype "passive"))
      (node (ref "D107") (pin "A") (pinfunction "A_A") (pintype "passive"))
      (node (ref "D108") (pin "A") (pinfunction "A_A") (pintype "passive"))
      (node (ref "D109") (pin "A") (pinfunction "A_A") (pintype "passive"))
      (node (ref "D110") (pin "C") (pinfunction "C_C") (pintype "passive"))
      (node (ref "H1") (pin "MOUNT") (pinfunction "MOUNT_MOUNT") (pintype "passive"))
      (node (ref "H2") (pin "MOUNT") (pinfunction "MOUNT_MOUNT") (pintype "passive"))
      (node (ref "H3") (pin "B3,2") (pinfunction "MOUNT_B3,2") (pintype "passive"))
      (node (ref "H4") (pin "B3,2") (pinfunction "MOUNT_B3,2") (pintype "passive"))
      (node (ref "H5") (pin "B3,2") (pinfunction "MOUNT_B3,2") (pintype "passive"))
      (node (ref "H6") (pin "B3,2") (pinfunction "MOUNT_B3,2") (pintype "passive"))
      (node (ref "H7") (pin "MOUNT") (pinfunction "MOUNT_MOUNT") (pintype "passive"))
      (node (ref "H8") (pin "MOUNT") (pinfunction "MOUNT_MOUNT") (pintype "passive"))
      (node (ref "IC1") (pin "F1_H1_B") (pinfunction "F1_H1_B_F1_H1_B") (pintype "bidirectional"))
      (node (ref "IC1") (pin "F2_H1_B") (pinfunction "F2_H1_B_F2_H1_B") (pintype "bidirectional"))
      (node (ref "IC1") (pin "F2_H2_B") (pinfunction "F2_H2_B_F2_H2_B") (pintype "bidirectional"))
      (node (ref "IC1") (pin "F3_H1_B") (pinfunction "F3_H1_B_F3_H1_B") (pintype "bidirectional"))
      (node (ref "IC1") (pin "F3_H2_B") (pinfunction "F3_H2_B_F3_H2_B") (pintype "bidirectional"))
      (node (ref "IC1") (pin "F3_H3_B") (pinfunction "F3_H3_B_F3_H3_B") (pintype "bidirectional"))
      (node (ref "IC1") (pin "F4_H1_B") (pinfunction "F4_H1_B_F4_H1_B") (pintype "bidirectional"))
      (node (ref "IC1") (pin "F4_H2_B") (pinfunction "F4_H2_B_F4_H2_B") (pintype "bidirectional"))
      (node (ref "IC1") (pin "F4_H3_B") (pinfunction "F4_H3_B_F4_H3_B") (pintype "bidirectional"))
      (node (ref "IC1") (pin "F4_H4_B") (pinfunction "F4_H4_B_F4_H4_B") (pintype "bidirectional"))
      (node (ref "IC1") (pin "HANDLE") (pinfunction "HANDLE_HANDLE") (pintype "bidirectional"))
      (node (ref "JP100") (pin "1") (pinfunction "1_1") (pintype "passive"))
      (node (ref "JP100") (pin "11") (pinfunction "11_11") (pintype "passive"))
      (node (ref "JP100") (pin "13") (pinfunction "13_13") (pintype "passive"))
      (node (ref "JP100") (pin "15") (pinfunction "15_15") (pintype "passive"))
      (node (ref "JP100") (pin "17") (pinfunction "17_17") (pintype "passive"))
      (node (ref "JP100") (pin "19") (pinfunction "19_19") (pintype "passive"))
      (node (ref "JP100") (pin "3") (pinfunction "3_3") (pintype "passive"))
      (node (ref "JP100") (pin "5") (pinfunction "5_5") (pintype "passive"))
      (node (ref "JP100") (pin "7") (pinfunction "7_7") (pintype "passive"))
      (node (ref "JP100") (pin "9") (pinfunction "9_9") (pintype "passive"))
      (node (ref "JP101") (pin "1") (pinfunction "1_1") (pintype "passive"))
      (node (ref "JP101") (pin "11") (pinfunction "11_11") (pintype "passive"))
      (node (ref "JP101") (pin "13") (pinfunction "13_13") (pintype "passive"))
      (node (ref "JP101") (pin "15") (pinfunction "15_15") (pintype "passive"))
      (node (ref "JP101") (pin "17") (pinfunction "17_17") (pintype "passive"))
      (node (ref "JP101") (pin "19") (pinfunction "19_19") (pintype "passive"))
      (node (ref "JP101") (pin "3") (pinfunction "3_3") (pintype "passive"))
      (node (ref "JP101") (pin "5") (pinfunction "5_5") (pintype "passive"))
      (node (ref "JP101") (pin "7") (pinfunction "7_7") (pintype "passive"))
      (node (ref "JP101") (pin "9") (pinfunction "9_9") (pintype "passive"))
      (node (ref "JP102") (pin "11") (pinfunction "11_11") (pintype "passive"))
      (node (ref "JP102") (pin "13") (pinfunction "13_13") (pintype "passive"))
      (node (ref "JP102") (pin "15") (pinfunction "15_15") (pintype "passive"))
      (node (ref "JP102") (pin "3") (pinfunction "3_3") (pintype "passive"))
      (node (ref "JP102") (pin "5") (pinfunction "5_5") (pintype "passive"))
      (node (ref "JP102") (pin "7") (pinfunction "7_7") (pintype "passive"))
      (node (ref "JP102") (pin "9") (pinfunction "9_9") (pintype "passive"))
      (node (ref "JP103") (pin "10") (pinfunction "10_10") (pintype "passive"))
      (node (ref "JP103") (pin "12") (pinfunction "12_12") (pintype "passive"))
      (node (ref "JP103") (pin "14") (pinfunction "14_14") (pintype "passive"))
      (node (ref "JP103") (pin "16") (pinfunction "16_16") (pintype "passive"))
      (node (ref "JP103") (pin "18") (pinfunction "18_18") (pintype "passive"))
      (node (ref "JP103") (pin "6") (pinfunction "6_6") (pintype "passive"))
      (node (ref "JP103") (pin "8") (pinfunction "8_8") (pintype "passive"))
      (node (ref "U1") (pin "3") (pinfunction "+IN_A_3") (pintype "input"))
      (node (ref "U1") (pin "4") (pinfunction "V-_4") (pintype "power_in"))
      (node (ref "U1") (pin "5") (pinfunction "+IN_B_5") (pintype "input"))
      (node (ref "U2") (pin "3") (pinfunction "+IN_A_3") (pintype "input"))
      (node (ref "U2") (pin "4") (pinfunction "V-_4") (pintype "power_in"))
      (node (ref "U2") (pin "5") (pinfunction "+IN_B_5") (pintype "input"))
      (node (ref "U3") (pin "3") (pinfunction "+IN_A_3") (pintype "input"))
      (node (ref "U3") (pin "4") (pinfunction "V-_4") (pintype "power_in"))
      (node (ref "U3") (pin "5") (pinfunction "+IN_B_5") (pintype "input"))
      (node (ref "U4") (pin "3") (pinfunction "+IN_A_3") (pintype "input"))
      (node (ref "U4") (pin "4") (pinfunction "V-_4") (pintype "power_in"))
      (node (ref "U4") (pin "5") (pinfunction "+IN_B_5") (pintype "input"))
      (node (ref "U5") (pin "3") (pinfunction "+IN_A_3") (pintype "input"))
      (node (ref "U5") (pin "4") (pinfunction "V-_4") (pintype "power_in"))
      (node (ref "U5") (pin "5") (pinfunction "+IN_B_5") (pintype "input"))
    )
  )
)
